# guest_room_controller_V1.net
KiCad netlist of a schematic drawn in EAGLE
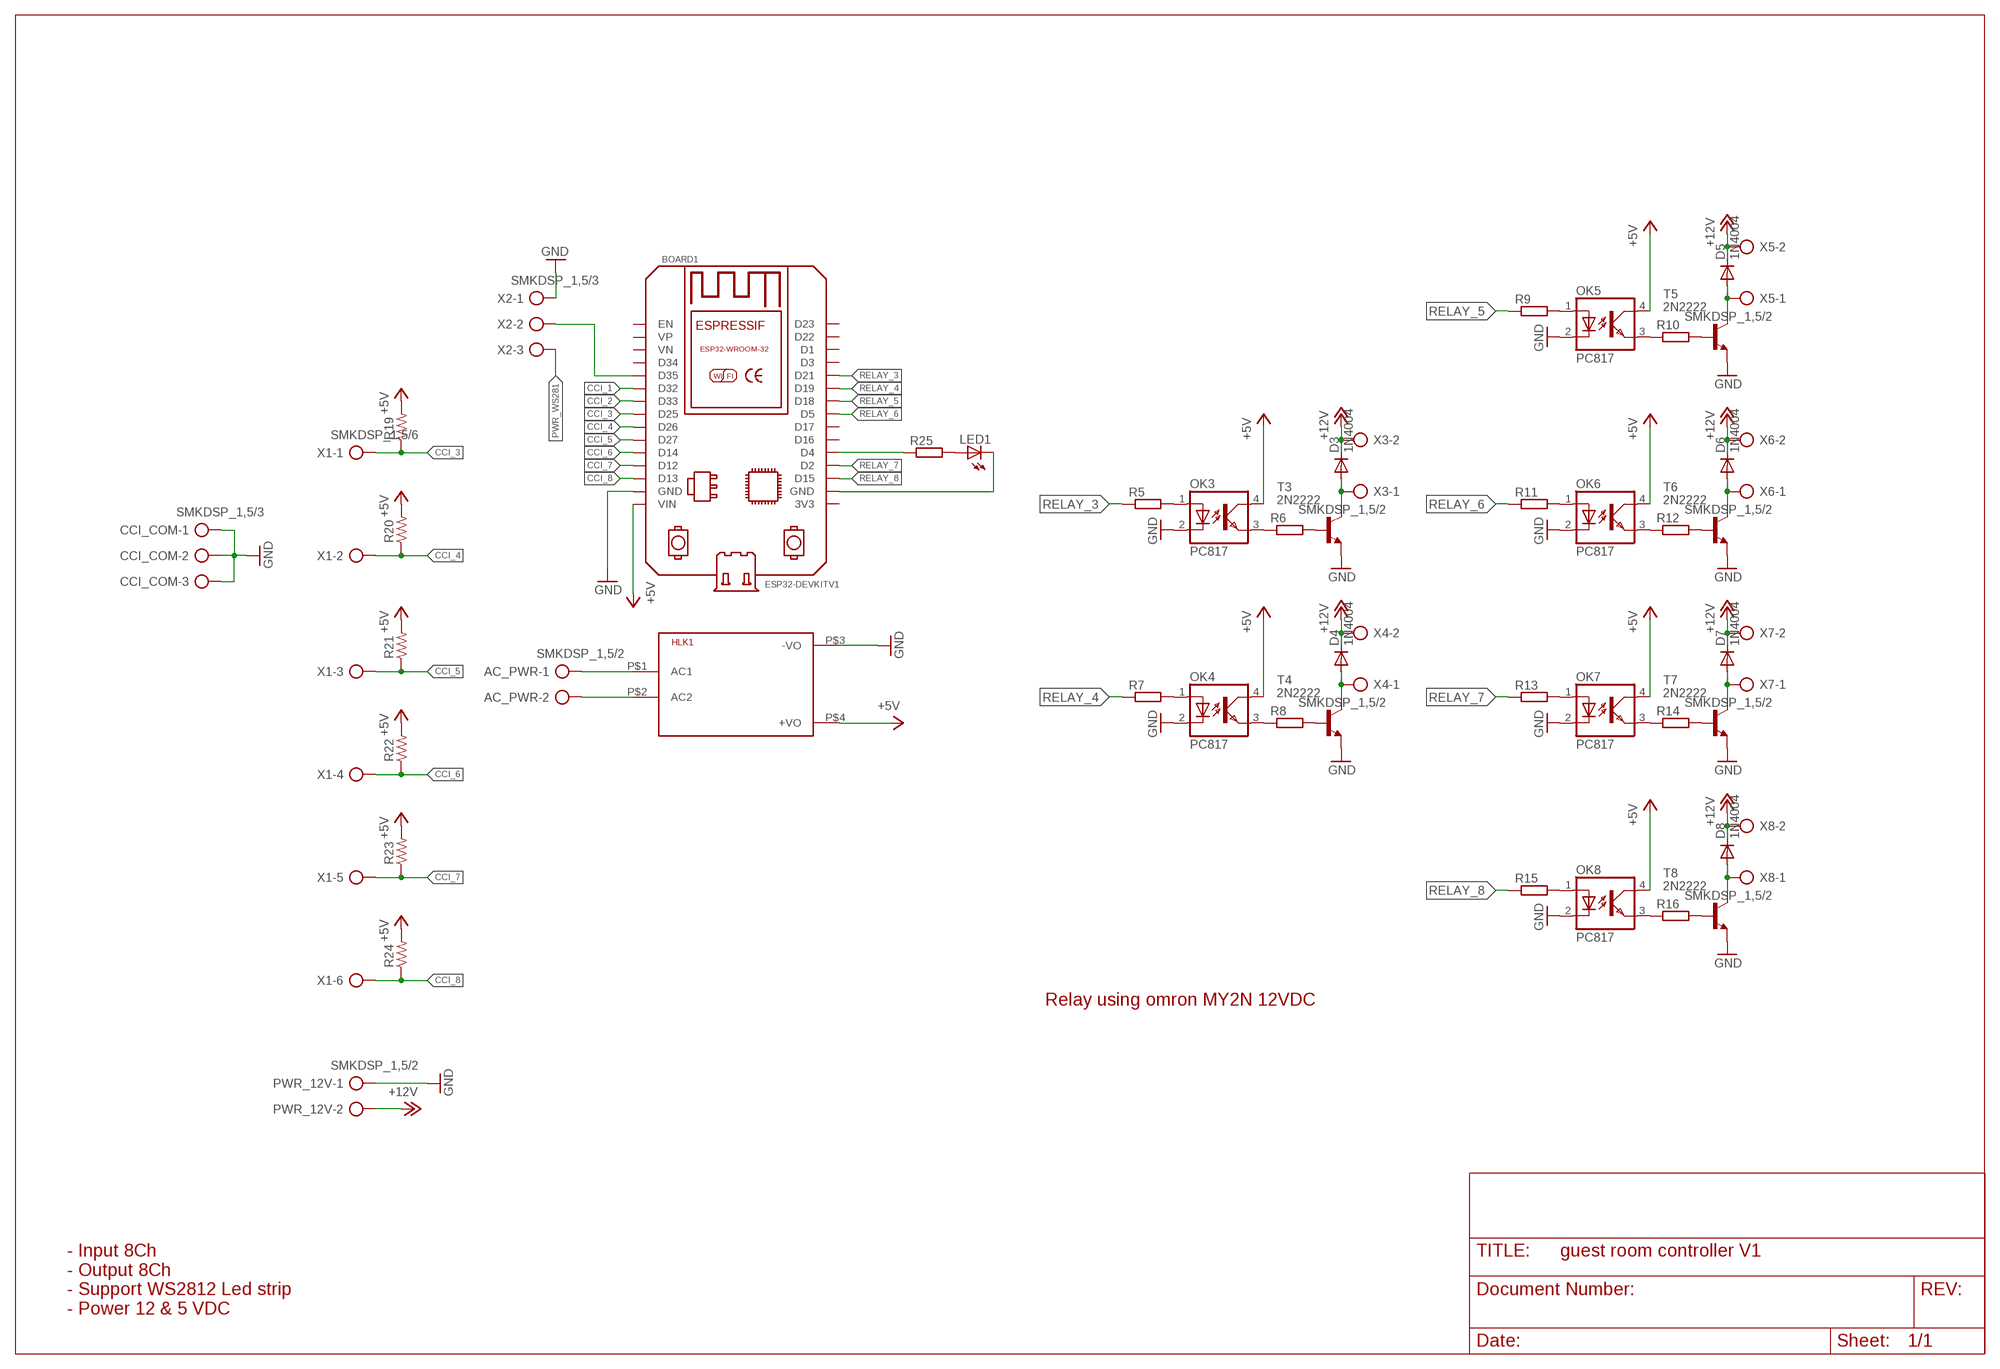
[diagram p0: schematic, sheet 1]

(export (version "E")
  (design (tool "Eeschema 10.0.6"))
  (components
    (comp (ref "AC_PWR")
      (value "SMKDSP_1,5/2")
      (footprint "eagle-import:SMKDSP_1,5_2")
      (fields (field (name "MF") "FARNELL") (field (name "MPN") "1733570"))
      (libsource (lib "eagle-import") (part "SMKDSP_1,5/2"))
    )
    (comp (ref "BOARD1")
      (value "ESP32DEVKITV1")
      (footprint "eagle-import:ESP32-DEVKITV1")
      (libsource (lib "eagle-import") (part "ESP32DEVKITV1"))
    )
    (comp (ref "CCI_COM")
      (value "SMKDSP_1,5/3")
      (footprint "eagle-import:SMKDSP_1,5_3")
      (fields (field (name "MF") "FARNELL") (field (name "MPN") "1733583"))
      (libsource (lib "eagle-import") (part "SMKDSP_1,5/3"))
    )
    (comp (ref "D3")
      (value "1N4004")
      (footprint "eagle-import:DO41-10")
      (libsource (lib "eagle-import") (part "1N4004"))
    )
    (comp (ref "D4")
      (value "1N4004")
      (footprint "eagle-import:DO41-10")
      (libsource (lib "eagle-import") (part "1N4004"))
    )
    (comp (ref "D5")
      (value "1N4004")
      (footprint "eagle-import:DO41-10")
      (libsource (lib "eagle-import") (part "1N4004"))
    )
    (comp (ref "D6")
      (value "1N4004")
      (footprint "eagle-import:DO41-10")
      (libsource (lib "eagle-import") (part "1N4004"))
    )
    (comp (ref "D7")
      (value "1N4004")
      (footprint "eagle-import:DO41-10")
      (libsource (lib "eagle-import") (part "1N4004"))
    )
    (comp (ref "D8")
      (value "1N4004")
      (footprint "eagle-import:DO41-10")
      (libsource (lib "eagle-import") (part "1N4004"))
    )
    (comp (ref "HLK1")
      (value "HLK-PM013W")
      (footprint "eagle-import:HLK-PM01")
      (libsource (lib "eagle-import") (part "HLK-PM013W"))
    )
    (comp (ref "LED1")
      (value "LED3MM")
      (footprint "eagle-import:LED3MM")
      (libsource (lib "eagle-import") (part "LED3MM"))
    )
    (comp (ref "OK3")
      (value "PC817")
      (footprint "eagle-import:DIL04")
      (fields (field (name "MPN") "PC817X4J000F"))
      (libsource (lib "eagle-import") (part "PC817"))
    )
    (comp (ref "OK4")
      (value "PC817")
      (footprint "eagle-import:DIL04")
      (fields (field (name "MPN") "PC817X4J000F"))
      (libsource (lib "eagle-import") (part "PC817"))
    )
    (comp (ref "OK5")
      (value "PC817")
      (footprint "eagle-import:DIL04")
      (fields (field (name "MPN") "PC817X4J000F"))
      (libsource (lib "eagle-import") (part "PC817"))
    )
    (comp (ref "OK6")
      (value "PC817")
      (footprint "eagle-import:DIL04")
      (fields (field (name "MPN") "PC817X4J000F"))
      (libsource (lib "eagle-import") (part "PC817"))
    )
    (comp (ref "OK7")
      (value "PC817")
      (footprint "eagle-import:DIL04")
      (fields (field (name "MPN") "PC817X4J000F"))
      (libsource (lib "eagle-import") (part "PC817"))
    )
    (comp (ref "OK8")
      (value "PC817")
      (footprint "eagle-import:DIL04")
      (fields (field (name "MPN") "PC817X4J000F"))
      (libsource (lib "eagle-import") (part "PC817"))
    )
    (comp (ref "PWR_12V")
      (value "SMKDSP_1,5/2")
      (footprint "eagle-import:SMKDSP_1,5_2")
      (fields (field (name "MF") "FARNELL") (field (name "MPN") "1733570"))
      (libsource (lib "eagle-import") (part "SMKDSP_1,5/2"))
    )
    (comp (ref "R5")
      (value "R-EU_0207/10")
      (footprint "eagle-import:0207_10")
      (libsource (lib "eagle-import") (part "R-EU_0207/10"))
    )
    (comp (ref "R6")
      (value "R-EU_0207/10")
      (footprint "eagle-import:0207_10")
      (libsource (lib "eagle-import") (part "R-EU_0207/10"))
    )
    (comp (ref "R7")
      (value "R-EU_0207/10")
      (footprint "eagle-import:0207_10")
      (libsource (lib "eagle-import") (part "R-EU_0207/10"))
    )
    (comp (ref "R8")
      (value "R-EU_0207/10")
      (footprint "eagle-import:0207_10")
      (libsource (lib "eagle-import") (part "R-EU_0207/10"))
    )
    (comp (ref "R9")
      (value "R-EU_0207/10")
      (footprint "eagle-import:0207_10")
      (libsource (lib "eagle-import") (part "R-EU_0207/10"))
    )
    (comp (ref "R10")
      (value "R-EU_0207/10")
      (footprint "eagle-import:0207_10")
      (libsource (lib "eagle-import") (part "R-EU_0207/10"))
    )
    (comp (ref "R11")
      (value "R-EU_0207/10")
      (footprint "eagle-import:0207_10")
      (libsource (lib "eagle-import") (part "R-EU_0207/10"))
    )
    (comp (ref "R12")
      (value "R-EU_0207/10")
      (footprint "eagle-import:0207_10")
      (libsource (lib "eagle-import") (part "R-EU_0207/10"))
    )
    (comp (ref "R13")
      (value "R-EU_0207/10")
      (footprint "eagle-import:0207_10")
      (libsource (lib "eagle-import") (part "R-EU_0207/10"))
    )
    (comp (ref "R14")
      (value "R-EU_0207/10")
      (footprint "eagle-import:0207_10")
      (libsource (lib "eagle-import") (part "R-EU_0207/10"))
    )
    (comp (ref "R15")
      (value "R-EU_0207/10")
      (footprint "eagle-import:0207_10")
      (libsource (lib "eagle-import") (part "R-EU_0207/10"))
    )
    (comp (ref "R16")
      (value "R-EU_0207/10")
      (footprint "eagle-import:0207_10")
      (libsource (lib "eagle-import") (part "R-EU_0207/10"))
    )
    (comp (ref "R19")
      (value "R_1206")
      (footprint "eagle-import:R1206")
      (libsource (lib "eagle-import") (part "R_1206"))
    )
    (comp (ref "R20")
      (value "R_1206")
      (footprint "eagle-import:R1206")
      (libsource (lib "eagle-import") (part "R_1206"))
    )
    (comp (ref "R21")
      (value "R_1206")
      (footprint "eagle-import:R1206")
      (libsource (lib "eagle-import") (part "R_1206"))
    )
    (comp (ref "R22")
      (value "R_1206")
      (footprint "eagle-import:R1206")
      (libsource (lib "eagle-import") (part "R_1206"))
    )
    (comp (ref "R23")
      (value "R_1206")
      (footprint "eagle-import:R1206")
      (libsource (lib "eagle-import") (part "R_1206"))
    )
    (comp (ref "R24")
      (value "R_1206")
      (footprint "eagle-import:R1206")
      (libsource (lib "eagle-import") (part "R_1206"))
    )
    (comp (ref "R25")
      (value "R-EU_0207/10")
      (footprint "eagle-import:0207_10")
      (libsource (lib "eagle-import") (part "R-EU_0207/10"))
    )
    (comp (ref "T3")
      (value "2N2222")
      (footprint "eagle-import:TO18")
      (libsource (lib "eagle-import") (part "2N2222"))
    )
    (comp (ref "T4")
      (value "2N2222")
      (footprint "eagle-import:TO18")
      (libsource (lib "eagle-import") (part "2N2222"))
    )
    (comp (ref "T5")
      (value "2N2222")
      (footprint "eagle-import:TO18")
      (libsource (lib "eagle-import") (part "2N2222"))
    )
    (comp (ref "T6")
      (value "2N2222")
      (footprint "eagle-import:TO18")
      (libsource (lib "eagle-import") (part "2N2222"))
    )
    (comp (ref "T7")
      (value "2N2222")
      (footprint "eagle-import:TO18")
      (libsource (lib "eagle-import") (part "2N2222"))
    )
    (comp (ref "T8")
      (value "2N2222")
      (footprint "eagle-import:TO18")
      (libsource (lib "eagle-import") (part "2N2222"))
    )
    (comp (ref "X1")
      (value "SMKDSP_1,5/6")
      (footprint "eagle-import:SMKDSP_1,5_6")
      (fields (field (name "MF") "FARNELL") (field (name "MPN") "1733619"))
      (libsource (lib "eagle-import") (part "SMKDSP_1,5/6"))
    )
    (comp (ref "X2")
      (value "SMKDSP_1,5/3")
      (footprint "eagle-import:SMKDSP_1,5_3")
      (fields (field (name "MF") "FARNELL") (field (name "MPN") "1733583"))
      (libsource (lib "eagle-import") (part "SMKDSP_1,5/3"))
    )
    (comp (ref "X3")
      (value "SMKDSP_1,5/2")
      (footprint "eagle-import:SMKDSP_1,5_2")
      (fields (field (name "MF") "FARNELL") (field (name "MPN") "1733570"))
      (libsource (lib "eagle-import") (part "SMKDSP_1,5/2"))
    )
    (comp (ref "X4")
      (value "SMKDSP_1,5/2")
      (footprint "eagle-import:SMKDSP_1,5_2")
      (fields (field (name "MF") "FARNELL") (field (name "MPN") "1733570"))
      (libsource (lib "eagle-import") (part "SMKDSP_1,5/2"))
    )
    (comp (ref "X5")
      (value "SMKDSP_1,5/2")
      (footprint "eagle-import:SMKDSP_1,5_2")
      (fields (field (name "MF") "FARNELL") (field (name "MPN") "1733570"))
      (libsource (lib "eagle-import") (part "SMKDSP_1,5/2"))
    )
    (comp (ref "X6")
      (value "SMKDSP_1,5/2")
      (footprint "eagle-import:SMKDSP_1,5_2")
      (fields (field (name "MF") "FARNELL") (field (name "MPN") "1733570"))
      (libsource (lib "eagle-import") (part "SMKDSP_1,5/2"))
    )
    (comp (ref "X7")
      (value "SMKDSP_1,5/2")
      (footprint "eagle-import:SMKDSP_1,5_2")
      (fields (field (name "MF") "FARNELL") (field (name "MPN") "1733570"))
      (libsource (lib "eagle-import") (part "SMKDSP_1,5/2"))
    )
    (comp (ref "X8")
      (value "SMKDSP_1,5/2")
      (footprint "eagle-import:SMKDSP_1,5_2")
      (fields (field (name "MF") "FARNELL") (field (name "MPN") "1733570"))
      (libsource (lib "eagle-import") (part "SMKDSP_1,5/2"))
    )
  )
  (nets
    (net (code "1") (name "+5V") (class "Default")
      (node (ref "BOARD1") (pin "VIN") (pinfunction "VIN_VIN") (pintype "bidirectional"))
      (node (ref "HLK1") (pin "P$4") (pinfunction "+VO_P$4") (pintype "bidirectional"))
      (node (ref "OK3") (pin "4") (pinfunction "COL_4") (pintype "passive"))
      (node (ref "OK4") (pin "4") (pinfunction "COL_4") (pintype "passive"))
      (node (ref "OK5") (pin "4") (pinfunction "COL_4") (pintype "passive"))
      (node (ref "OK6") (pin "4") (pinfunction "COL_4") (pintype "passive"))
      (node (ref "OK7") (pin "4") (pinfunction "COL_4") (pintype "passive"))
      (node (ref "OK8") (pin "4") (pinfunction "COL_4") (pintype "passive"))
      (node (ref "R19") (pin "2") (pinfunction "2_2") (pintype "passive"))
      (node (ref "R20") (pin "2") (pinfunction "2_2") (pintype "passive"))
      (node (ref "R21") (pin "2") (pinfunction "2_2") (pintype "passive"))
      (node (ref "R22") (pin "2") (pinfunction "2_2") (pintype "passive"))
      (node (ref "R23") (pin "2") (pinfunction "2_2") (pintype "passive"))
      (node (ref "R24") (pin "2") (pinfunction "2_2") (pintype "passive"))
    )
    (net (code "2") (name "+12V") (class "Default")
      (node (ref "D3") (pin "C") (pinfunction "C_C") (pintype "passive"))
      (node (ref "D4") (pin "C") (pinfunction "C_C") (pintype "passive"))
      (node (ref "D5") (pin "C") (pinfunction "C_C") (pintype "passive"))
      (node (ref "D6") (pin "C") (pinfunction "C_C") (pintype "passive"))
      (node (ref "D7") (pin "C") (pinfunction "C_C") (pintype "passive"))
      (node (ref "D8") (pin "C") (pinfunction "C_C") (pintype "passive"))
      (node (ref "PWR_12V") (pin "2") (pinfunction "KL_2") (pintype "passive"))
      (node (ref "X3") (pin "2") (pinfunction "KL_2") (pintype "passive"))
      (node (ref "X4") (pin "2") (pinfunction "KL_2") (pintype "passive"))
      (node (ref "X5") (pin "2") (pinfunction "KL_2") (pintype "passive"))
      (node (ref "X6") (pin "2") (pinfunction "KL_2") (pintype "passive"))
      (node (ref "X7") (pin "2") (pinfunction "KL_2") (pintype "passive"))
      (node (ref "X8") (pin "2") (pinfunction "KL_2") (pintype "passive"))
    )
    (net (code "3") (name "CCI_1") (class "Default")
      (node (ref "BOARD1") (pin "D32") (pinfunction "D32_D32") (pintype "bidirectional"))
    )
    (net (code "4") (name "CCI_2") (class "Default")
      (node (ref "BOARD1") (pin "D33") (pinfunction "D33_D33") (pintype "bidirectional"))
    )
    (net (code "5") (name "CCI_3") (class "Default")
      (node (ref "BOARD1") (pin "D25") (pinfunction "D25_D25") (pintype "bidirectional"))
      (node (ref "R19") (pin "1") (pinfunction "1_1") (pintype "passive"))
      (node (ref "X1") (pin "1") (pinfunction "KL_1") (pintype "passive"))
    )
    (net (code "6") (name "CCI_4") (class "Default")
      (node (ref "BOARD1") (pin "D26") (pinfunction "D26_D26") (pintype "bidirectional"))
      (node (ref "R20") (pin "1") (pinfunction "1_1") (pintype "passive"))
      (node (ref "X1") (pin "2") (pinfunction "KL_2") (pintype "passive"))
    )
    (net (code "7") (name "CCI_5") (class "Default")
      (node (ref "BOARD1") (pin "D27") (pinfunction "D27_D27") (pintype "bidirectional"))
      (node (ref "R21") (pin "1") (pinfunction "1_1") (pintype "passive"))
      (node (ref "X1") (pin "3") (pinfunction "KL_3") (pintype "passive"))
    )
    (net (code "8") (name "CCI_6") (class "Default")
      (node (ref "BOARD1") (pin "D14") (pinfunction "D14_D14") (pintype "bidirectional"))
      (node (ref "R22") (pin "1") (pinfunction "1_1") (pintype "passive"))
      (node (ref "X1") (pin "4") (pinfunction "KL_4") (pintype "passive"))
    )
    (net (code "9") (name "CCI_7") (class "Default")
      (node (ref "BOARD1") (pin "D12") (pinfunction "D12_D12") (pintype "bidirectional"))
      (node (ref "R23") (pin "1") (pinfunction "1_1") (pintype "passive"))
      (node (ref "X1") (pin "5") (pinfunction "KL_5") (pintype "passive"))
    )
    (net (code "10") (name "CCI_8") (class "Default")
      (node (ref "BOARD1") (pin "D13") (pinfunction "D13_D13") (pintype "bidirectional"))
      (node (ref "R24") (pin "1") (pinfunction "1_1") (pintype "passive"))
      (node (ref "X1") (pin "6") (pinfunction "KL_6") (pintype "passive"))
    )
    (net (code "11") (name "GND") (class "Default")
      (node (ref "BOARD1") (pin "GND") (pinfunction "GND_GND") (pintype "bidirectional"))
      (node (ref "CCI_COM") (pin "1") (pinfunction "KL_1") (pintype "passive"))
      (node (ref "CCI_COM") (pin "2") (pinfunction "KL_2") (pintype "passive"))
      (node (ref "CCI_COM") (pin "3") (pinfunction "KL_3") (pintype "passive"))
      (node (ref "HLK1") (pin "P$3") (pinfunction "-VO_P$3") (pintype "bidirectional"))
      (node (ref "OK3") (pin "2") (pinfunction "C_2") (pintype "passive"))
      (node (ref "OK4") (pin "2") (pinfunction "C_2") (pintype "passive"))
      (node (ref "OK5") (pin "2") (pinfunction "C_2") (pintype "passive"))
      (node (ref "OK6") (pin "2") (pinfunction "C_2") (pintype "passive"))
      (node (ref "OK7") (pin "2") (pinfunction "C_2") (pintype "passive"))
      (node (ref "OK8") (pin "2") (pinfunction "C_2") (pintype "passive"))
      (node (ref "PWR_12V") (pin "1") (pinfunction "KL_1") (pintype "passive"))
      (node (ref "T3") (pin "1") (pinfunction "E_1") (pintype "passive"))
      (node (ref "T4") (pin "1") (pinfunction "E_1") (pintype "passive"))
      (node (ref "T5") (pin "1") (pinfunction "E_1") (pintype "passive"))
      (node (ref "T6") (pin "1") (pinfunction "E_1") (pintype "passive"))
      (node (ref "T7") (pin "1") (pinfunction "E_1") (pintype "passive"))
      (node (ref "T8") (pin "1") (pinfunction "E_1") (pintype "passive"))
      (node (ref "X2") (pin "1") (pinfunction "KL_1") (pintype "passive"))
    )
    (net (code "12") (name "Net-(AC_PWRA-KL)") (class "Default")
      (node (ref "AC_PWR") (pin "1") (pinfunction "KL_1") (pintype "passive"))
      (node (ref "HLK1") (pin "P$1") (pinfunction "AC1_P$1") (pintype "bidirectional"))
    )
    (net (code "13") (name "Net-(AC_PWRB-KL)") (class "Default")
      (node (ref "AC_PWR") (pin "2") (pinfunction "KL_2") (pintype "passive"))
      (node (ref "HLK1") (pin "P$2") (pinfunction "AC2_P$2") (pintype "bidirectional"))
    )
    (net (code "14") (name "Net-(BOARD1-PadD4)") (class "Default")
      (node (ref "BOARD1") (pin "D4") (pinfunction "D4_D4") (pintype "bidirectional"))
      (node (ref "R25") (pin "1") (pinfunction "1_1") (pintype "passive"))
    )
    (net (code "15") (name "Net-(LED1-C)") (class "Default")
      (node (ref "BOARD1") (pin "GND@1") (pinfunction "GND_GND@1") (pintype "bidirectional"))
      (node (ref "LED1") (pin "K") (pinfunction "C_K") (pintype "passive"))
    )
    (net (code "16") (name "Net-(LED1-PadA)") (class "Default")
      (node (ref "LED1") (pin "A") (pinfunction "A_A") (pintype "passive"))
      (node (ref "R25") (pin "2") (pinfunction "2_2") (pintype "passive"))
    )
    (net (code "17") (name "Net-(OK3-A)") (class "Default")
      (node (ref "OK3") (pin "1") (pinfunction "A_1") (pintype "passive"))
      (node (ref "R5") (pin "2") (pinfunction "2_2") (pintype "passive"))
    )
    (net (code "18") (name "Net-(OK3-EMIT)") (class "Default")
      (node (ref "OK3") (pin "3") (pinfunction "EMIT_3") (pintype "passive"))
      (node (ref "R6") (pin "1") (pinfunction "1_1") (pintype "passive"))
    )
    (net (code "19") (name "Net-(OK4-A)") (class "Default")
      (node (ref "OK4") (pin "1") (pinfunction "A_1") (pintype "passive"))
      (node (ref "R7") (pin "2") (pinfunction "2_2") (pintype "passive"))
    )
    (net (code "20") (name "Net-(OK4-EMIT)") (class "Default")
      (node (ref "OK4") (pin "3") (pinfunction "EMIT_3") (pintype "passive"))
      (node (ref "R8") (pin "1") (pinfunction "1_1") (pintype "passive"))
    )
    (net (code "21") (name "Net-(OK5-A)") (class "Default")
      (node (ref "OK5") (pin "1") (pinfunction "A_1") (pintype "passive"))
      (node (ref "R9") (pin "2") (pinfunction "2_2") (pintype "passive"))
    )
    (net (code "22") (name "Net-(OK5-EMIT)") (class "Default")
      (node (ref "OK5") (pin "3") (pinfunction "EMIT_3") (pintype "passive"))
      (node (ref "R10") (pin "1") (pinfunction "1_1") (pintype "passive"))
    )
    (net (code "23") (name "Net-(OK6-A)") (class "Default")
      (node (ref "OK6") (pin "1") (pinfunction "A_1") (pintype "passive"))
      (node (ref "R11") (pin "2") (pinfunction "2_2") (pintype "passive"))
    )
    (net (code "24") (name "Net-(OK6-EMIT)") (class "Default")
      (node (ref "OK6") (pin "3") (pinfunction "EMIT_3") (pintype "passive"))
      (node (ref "R12") (pin "1") (pinfunction "1_1") (pintype "passive"))
    )
    (net (code "25") (name "Net-(OK7-A)") (class "Default")
      (node (ref "OK7") (pin "1") (pinfunction "A_1") (pintype "passive"))
      (node (ref "R13") (pin "2") (pinfunction "2_2") (pintype "passive"))
    )
    (net (code "26") (name "Net-(OK7-EMIT)") (class "Default")
      (node (ref "OK7") (pin "3") (pinfunction "EMIT_3") (pintype "passive"))
      (node (ref "R14") (pin "1") (pinfunction "1_1") (pintype "passive"))
    )
    (net (code "27") (name "Net-(OK8-A)") (class "Default")
      (node (ref "OK8") (pin "1") (pinfunction "A_1") (pintype "passive"))
      (node (ref "R15") (pin "2") (pinfunction "2_2") (pintype "passive"))
    )
    (net (code "28") (name "Net-(OK8-EMIT)") (class "Default")
      (node (ref "OK8") (pin "3") (pinfunction "EMIT_3") (pintype "passive"))
      (node (ref "R16") (pin "1") (pinfunction "1_1") (pintype "passive"))
    )
    (net (code "29") (name "Net-(T3-B)") (class "Default")
      (node (ref "R6") (pin "2") (pinfunction "2_2") (pintype "passive"))
      (node (ref "T3") (pin "2") (pinfunction "B_2") (pintype "passive"))
    )
    (net (code "30") (name "Net-(T3-C)") (class "Default")
      (node (ref "D3") (pin "A") (pinfunction "A_A") (pintype "passive"))
      (node (ref "T3") (pin "3") (pinfunction "C_3") (pintype "passive"))
      (node (ref "X3") (pin "1") (pinfunction "KL_1") (pintype "passive"))
    )
    (net (code "31") (name "Net-(T4-B)") (class "Default")
      (node (ref "R8") (pin "2") (pinfunction "2_2") (pintype "passive"))
      (node (ref "T4") (pin "2") (pinfunction "B_2") (pintype "passive"))
    )
    (net (code "32") (name "Net-(T4-C)") (class "Default")
      (node (ref "D4") (pin "A") (pinfunction "A_A") (pintype "passive"))
      (node (ref "T4") (pin "3") (pinfunction "C_3") (pintype "passive"))
      (node (ref "X4") (pin "1") (pinfunction "KL_1") (pintype "passive"))
    )
    (net (code "33") (name "Net-(T5-B)") (class "Default")
      (node (ref "R10") (pin "2") (pinfunction "2_2") (pintype "passive"))
      (node (ref "T5") (pin "2") (pinfunction "B_2") (pintype "passive"))
    )
    (net (code "34") (name "Net-(T5-C)") (class "Default")
      (node (ref "D5") (pin "A") (pinfunction "A_A") (pintype "passive"))
      (node (ref "T5") (pin "3") (pinfunction "C_3") (pintype "passive"))
      (node (ref "X5") (pin "1") (pinfunction "KL_1") (pintype "passive"))
    )
    (net (code "35") (name "Net-(T6-B)") (class "Default")
      (node (ref "R12") (pin "2") (pinfunction "2_2") (pintype "passive"))
      (node (ref "T6") (pin "2") (pinfunction "B_2") (pintype "passive"))
    )
    (net (code "36") (name "Net-(T6-C)") (class "Default")
      (node (ref "D6") (pin "A") (pinfunction "A_A") (pintype "passive"))
      (node (ref "T6") (pin "3") (pinfunction "C_3") (pintype "passive"))
      (node (ref "X6") (pin "1") (pinfunction "KL_1") (pintype "passive"))
    )
    (net (code "37") (name "Net-(T7-B)") (class "Default")
      (node (ref "R14") (pin "2") (pinfunction "2_2") (pintype "passive"))
      (node (ref "T7") (pin "2") (pinfunction "B_2") (pintype "passive"))
    )
    (net (code "38") (name "Net-(T7-C)") (class "Default")
      (node (ref "D7") (pin "A") (pinfunction "A_A") (pintype "passive"))
      (node (ref "T7") (pin "3") (pinfunction "C_3") (pintype "passive"))
      (node (ref "X7") (pin "1") (pinfunction "KL_1") (pintype "passive"))
    )
    (net (code "39") (name "Net-(T8-B)") (class "Default")
      (node (ref "R16") (pin "2") (pinfunction "2_2") (pintype "passive"))
      (node (ref "T8") (pin "2") (pinfunction "B_2") (pintype "passive"))
    )
    (net (code "40") (name "Net-(T8-C)") (class "Default")
      (node (ref "D8") (pin "A") (pinfunction "A_A") (pintype "passive"))
      (node (ref "T8") (pin "3") (pinfunction "C_3") (pintype "passive"))
      (node (ref "X8") (pin "1") (pinfunction "KL_1") (pintype "passive"))
    )
    (net (code "41") (name "Net-(X2B-KL)") (class "Default")
      (node (ref "BOARD1") (pin "D35") (pinfunction "D35_D35") (pintype "bidirectional"))
      (node (ref "X2") (pin "2") (pinfunction "KL_2") (pintype "passive"))
    )
    (net (code "42") (name "PWR_WS281") (class "Default")
      (node (ref "X2") (pin "3") (pinfunction "KL_3") (pintype "passive"))
    )
    (net (code "43") (name "RELAY_3") (class "Default")
      (node (ref "BOARD1") (pin "D21") (pinfunction "D21_D21") (pintype "bidirectional"))
      (node (ref "R5") (pin "1") (pinfunction "1_1") (pintype "passive"))
    )
    (net (code "44") (name "RELAY_4") (class "Default")
      (node (ref "BOARD1") (pin "D19") (pinfunction "D19_D19") (pintype "bidirectional"))
      (node (ref "R7") (pin "1") (pinfunction "1_1") (pintype "passive"))
    )
    (net (code "45") (name "RELAY_5") (class "Default")
      (node (ref "BOARD1") (pin "D18") (pinfunction "D18_D18") (pintype "bidirectional"))
      (node (ref "R9") (pin "1") (pinfunction "1_1") (pintype "passive"))
    )
    (net (code "46") (name "RELAY_6") (class "Default")
      (node (ref "BOARD1") (pin "D5") (pinfunction "D5_D5") (pintype "bidirectional"))
      (node (ref "R11") (pin "1") (pinfunction "1_1") (pintype "passive"))
    )
    (net (code "47") (name "RELAY_7") (class "Default")
      (node (ref "BOARD1") (pin "D2") (pinfunction "D2_D2") (pintype "bidirectional"))
      (node (ref "R13") (pin "1") (pinfunction "1_1") (pintype "passive"))
    )
    (net (code "48") (name "RELAY_8") (class "Default")
      (node (ref "BOARD1") (pin "D15") (pinfunction "D15_D15") (pintype "bidirectional"))
      (node (ref "R15") (pin "1") (pinfunction "1_1") (pintype "passive"))
    )
    (net (code "49") (name "unconnected-(BOARD1-Pad3V3)") (class "Default")
      (node (ref "BOARD1") (pin "3V3") (pinfunction "3V3_3V3") (pintype "bidirectional"))
    )
    (net (code "50") (name "unconnected-(BOARD1-PadD1)") (class "Default")
      (node (ref "BOARD1") (pin "D1") (pinfunction "D1_D1") (pintype "bidirectional"))
    )
    (net (code "51") (name "unconnected-(BOARD1-PadD3)") (class "Default")
      (node (ref "BOARD1") (pin "D3") (pinfunction "D3_D3") (pintype "bidirectional"))
    )
    (net (code "52") (name "unconnected-(BOARD1-PadD16)") (class "Default")
      (node (ref "BOARD1") (pin "D16") (pinfunction "D16_D16") (pintype "bidirectional"))
    )
    (net (code "53") (name "unconnected-(BOARD1-PadD17)") (class "Default")
      (node (ref "BOARD1") (pin "D17") (pinfunction "D17_D17") (pintype "bidirectional"))
    )
    (net (code "54") (name "unconnected-(BOARD1-PadD22)") (class "Default")
      (node (ref "BOARD1") (pin "D22") (pinfunction "D22_D22") (pintype "bidirectional"))
    )
    (net (code "55") (name "unconnected-(BOARD1-PadD23)") (class "Default")
      (node (ref "BOARD1") (pin "D23") (pinfunction "D23_D23") (pintype "bidirectional"))
    )
    (net (code "56") (name "unconnected-(BOARD1-PadD34)") (class "Default")
      (node (ref "BOARD1") (pin "D34") (pinfunction "D34_D34") (pintype "bidirectional"))
    )
    (net (code "57") (name "unconnected-(BOARD1-PadEN)") (class "Default")
      (node (ref "BOARD1") (pin "EN") (pinfunction "EN_EN") (pintype "bidirectional"))
    )
    (net (code "58") (name "unconnected-(BOARD1-PadVN)") (class "Default")
      (node (ref "BOARD1") (pin "VN") (pinfunction "VN_VN") (pintype "bidirectional"))
    )
    (net (code "59") (name "unconnected-(BOARD1-PadVP)") (class "Default")
      (node (ref "BOARD1") (pin "VP") (pinfunction "VP_VP") (pintype "bidirectional"))
    )
  )
)
